# BMS_Gauges_and_measure.net
KiCad netlist of a schematic drawn in Altium Designer
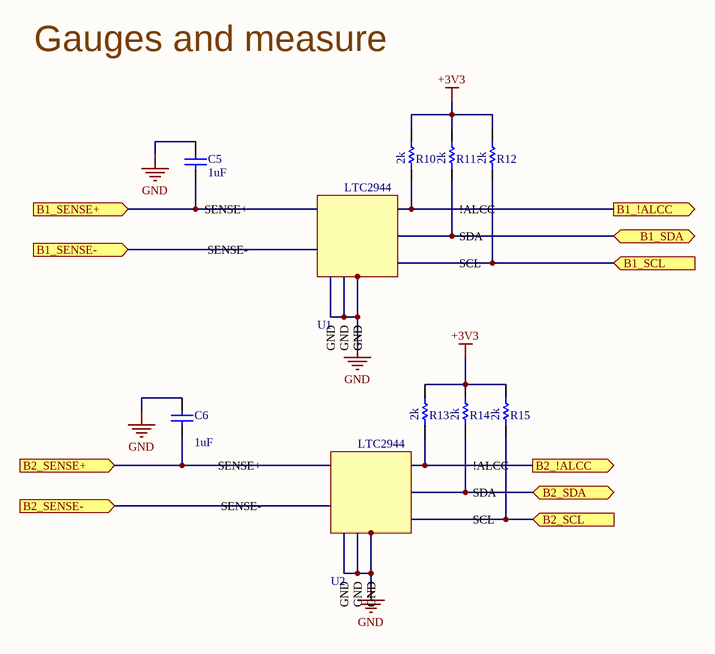
[diagram p0: BMS_Gauges_and_measure.SchDoc]

(export (version "E")
  (design (tool "Eeschema 10.0.6"))
  (components
    (comp (ref "C5")
      (value "1uF")
      (footprint "C0805")
      (description "Capacitor")
      (fields (field (name "Comment") "Cap_1") (field (name "PUBLISHER") "Altium Limited"))
      (libsource (lib "BMS_Schematic") (part "Cap_1"))
    )
    (comp (ref "C6")
      (value "1uF")
      (footprint "C0805")
      (description "Capacitor")
      (fields (field (name "Comment") "Cap_1") (field (name "PUBLISHER") "Altium Limited"))
      (libsource (lib "BMS_Schematic") (part "Cap_1"))
    )
    (comp (ref "R10")
      (value "Res_2k")
      (footprint "C0805")
      (description "Resistor")
      (libsource (lib "BMS_Schematic") (part "Res_2k"))
    )
    (comp (ref "R11")
      (value "Res_2k")
      (footprint "C0805")
      (description "Resistor")
      (libsource (lib "BMS_Schematic") (part "Res_2k"))
    )
    (comp (ref "R12")
      (value "Res_2k")
      (footprint "C0805")
      (description "Resistor")
      (libsource (lib "BMS_Schematic") (part "Res_2k"))
    )
    (comp (ref "R13")
      (value "Res_2k")
      (footprint "C0805")
      (description "Resistor")
      (libsource (lib "BMS_Schematic") (part "Res_2k"))
    )
    (comp (ref "R14")
      (value "Res_2k")
      (footprint "C0805")
      (description "Resistor")
      (libsource (lib "BMS_Schematic") (part "Res_2k"))
    )
    (comp (ref "R15")
      (value "Res_2k")
      (footprint "C0805")
      (description "Resistor")
      (libsource (lib "BMS_Schematic") (part "Res_2k"))
    )
    (comp (ref "U1")
      (value "LTC2944")
      (footprint "DFN-8_DD_Gauges")
      (description "Gas gauge")
      (libsource (lib "BMS_Schematic") (part "LTC2944"))
    )
    (comp (ref "U2")
      (value "LTC2944")
      (footprint "DFN-8_DD_Gauges")
      (description "Gas gauge")
      (libsource (lib "BMS_Schematic") (part "LTC2944"))
    )
  )
  (nets
    (net (code "1") (name "+3V3") (class "Default")
      (node (ref "R10") (pin "2") (pinfunction "2_2") (pintype "passive"))
      (node (ref "R11") (pin "2") (pinfunction "2_2") (pintype "passive"))
      (node (ref "R12") (pin "2") (pinfunction "2_2") (pintype "passive"))
      (node (ref "R13") (pin "2") (pinfunction "2_2") (pintype "passive"))
      (node (ref "R14") (pin "2") (pinfunction "2_2") (pintype "passive"))
      (node (ref "R15") (pin "2") (pinfunction "2_2") (pintype "passive"))
    )
    (net (code "2") (name "/B1_!ALCC") (class "Default")
      (node (ref "R10") (pin "1") (pinfunction "1_1") (pintype "passive"))
      (node (ref "U1") (pin "6") (pinfunction "!ALCC_6") (pintype "passive"))
    )
    (net (code "3") (name "/B1_SCL") (class "Default")
      (node (ref "R12") (pin "1") (pinfunction "1_1") (pintype "passive"))
      (node (ref "U1") (pin "4") (pinfunction "SCL_4") (pintype "passive"))
    )
    (net (code "4") (name "/B1_SDA") (class "Default")
      (node (ref "R11") (pin "1") (pinfunction "1_1") (pintype "passive"))
      (node (ref "U1") (pin "5") (pinfunction "SDA_5") (pintype "passive"))
    )
    (net (code "5") (name "/B1_SENSE+") (class "Default")
      (node (ref "C5") (pin "1") (pinfunction "1_1") (pintype "passive"))
      (node (ref "U1") (pin "1") (pinfunction "SENSE+_1") (pintype "passive"))
    )
    (net (code "6") (name "/B1_SENSE-") (class "Default")
      (node (ref "U1") (pin "8") (pinfunction "SENSE-_8") (pintype "passive"))
    )
    (net (code "7") (name "/B2_!ALCC") (class "Default")
      (node (ref "R13") (pin "1") (pinfunction "1_1") (pintype "passive"))
      (node (ref "U2") (pin "6") (pinfunction "!ALCC_6") (pintype "passive"))
    )
    (net (code "8") (name "/B2_SCL") (class "Default")
      (node (ref "R15") (pin "1") (pinfunction "1_1") (pintype "passive"))
      (node (ref "U2") (pin "4") (pinfunction "SCL_4") (pintype "passive"))
    )
    (net (code "9") (name "/B2_SDA") (class "Default")
      (node (ref "R14") (pin "1") (pinfunction "1_1") (pintype "passive"))
      (node (ref "U2") (pin "5") (pinfunction "SDA_5") (pintype "passive"))
    )
    (net (code "10") (name "/B2_SENSE+") (class "Default")
      (node (ref "C6") (pin "1") (pinfunction "1_1") (pintype "passive"))
      (node (ref "U2") (pin "1") (pinfunction "SENSE+_1") (pintype "passive"))
    )
    (net (code "11") (name "/B2_SENSE-") (class "Default")
      (node (ref "U2") (pin "8") (pinfunction "SENSE-_8") (pintype "passive"))
    )
    (net (code "12") (name "GND") (class "Default")
      (node (ref "C5") (pin "2") (pinfunction "2_2") (pintype "passive"))
      (node (ref "C6") (pin "2") (pinfunction "2_2") (pintype "passive"))
      (node (ref "U1") (pin "2") (pinfunction "GND_2") (pintype "passive"))
      (node (ref "U1") (pin "3") (pinfunction "GND_3") (pintype "passive"))
      (node (ref "U1") (pin "7") (pinfunction "GND_7") (pintype "passive"))
      (node (ref "U1") (pin "9") (pinfunction "GND_9") (pintype "passive"))
      (node (ref "U2") (pin "2") (pinfunction "GND_2") (pintype "passive"))
      (node (ref "U2") (pin "3") (pinfunction "GND_3") (pintype "passive"))
      (node (ref "U2") (pin "7") (pinfunction "GND_7") (pintype "passive"))
      (node (ref "U2") (pin "9") (pinfunction "GND_9") (pintype "passive"))
    )
  )
)
